# Gas.net
KiCad netlist of a schematic drawn in EAGLE
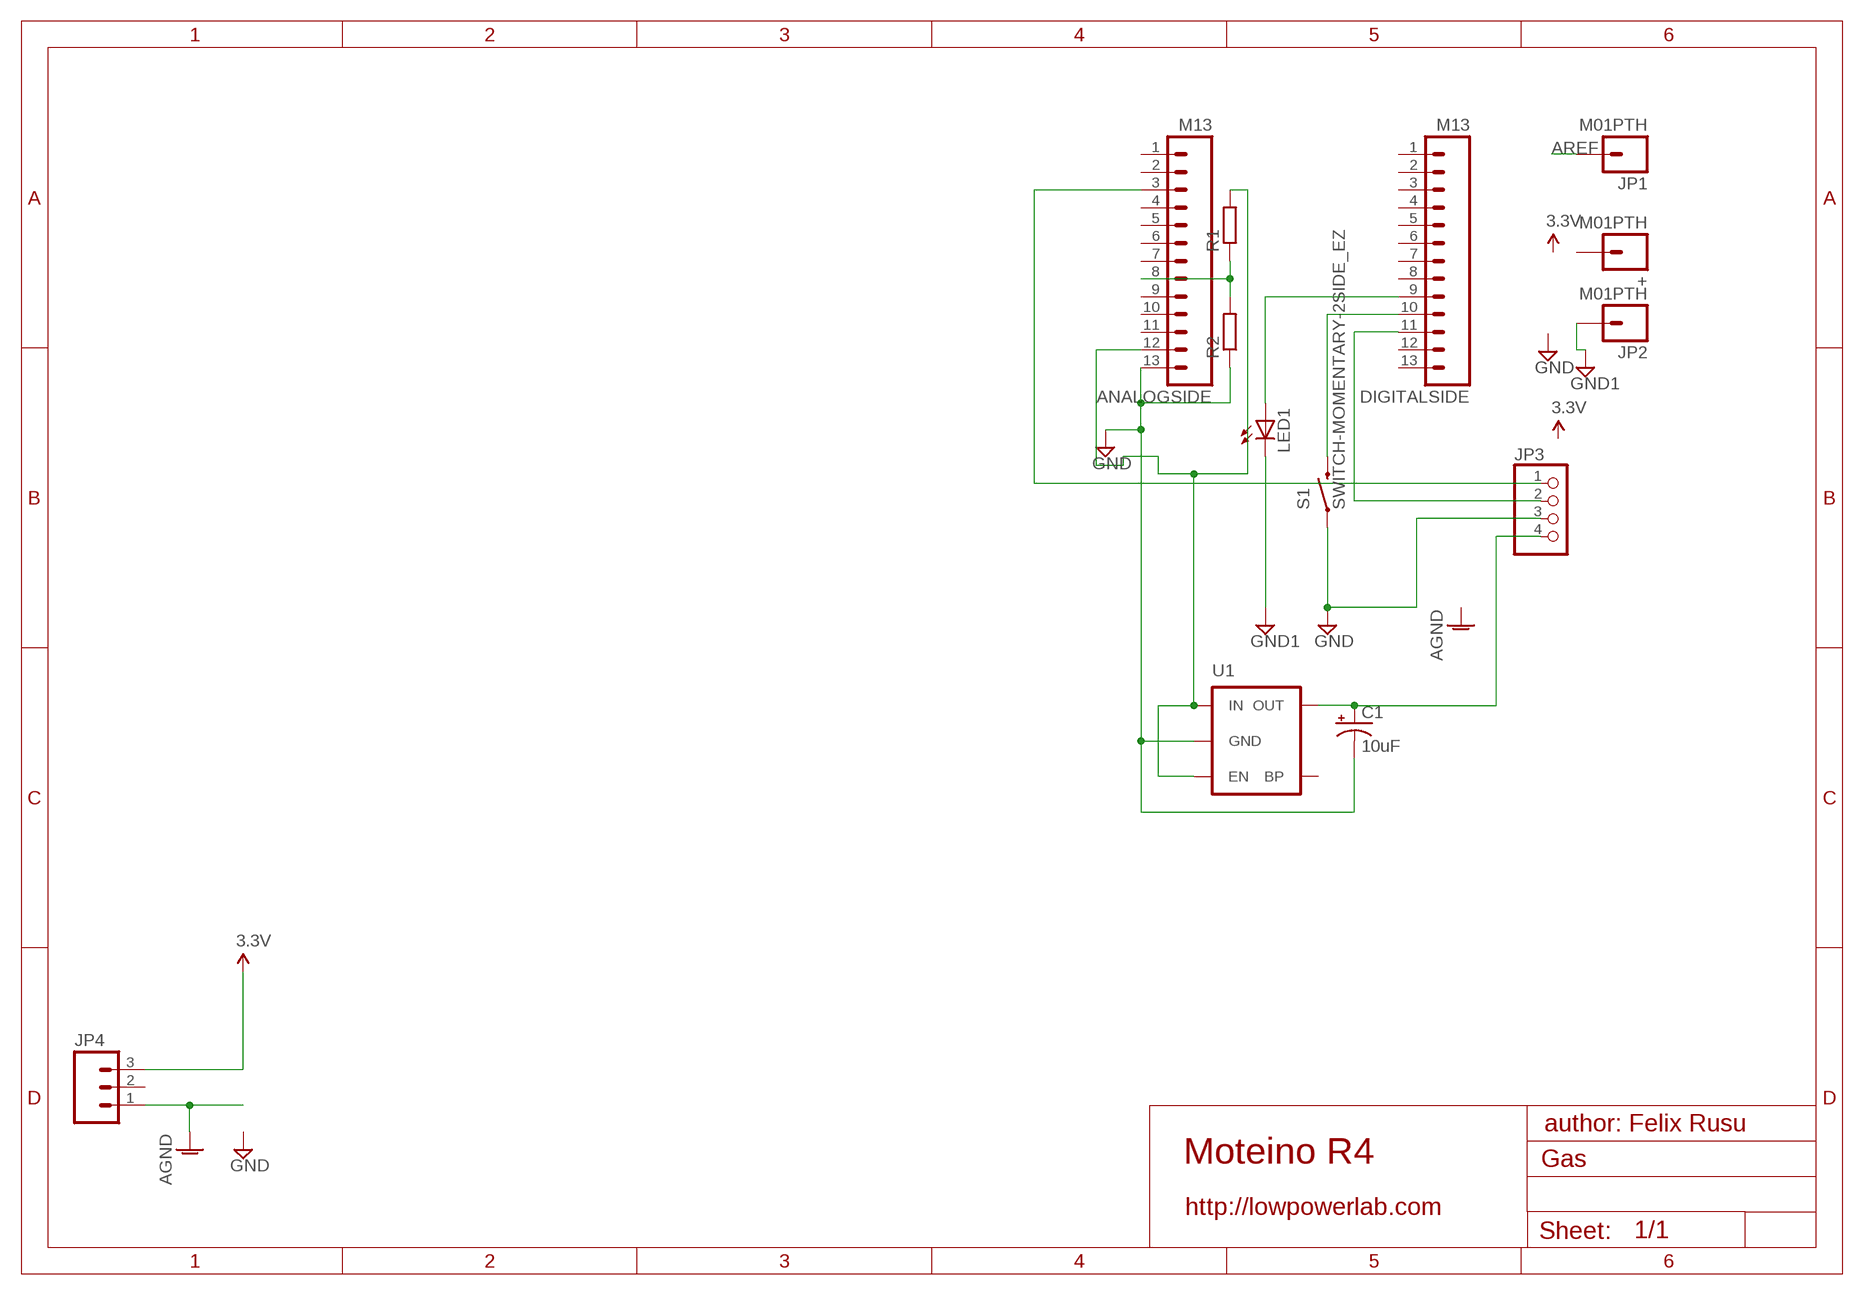
[diagram p0: schematic, sheet 1]

(export (version "E")
  (design (tool "Eeschema 10.0.6"))
  (components
    (comp (ref "+")
      (value "M01PTH")
      (footprint "eagle-import:1X01")
      (libsource (lib "eagle-import") (part "M01PTH"))
    )
    (comp (ref "ANALOGSIDE")
      (value "M13")
      (footprint "eagle-import:1X13")
      (libsource (lib "eagle-import") (part "M13"))
    )
    (comp (ref "C1")
      (value "10uF")
      (footprint "eagle-import:EIA3216")
      (libsource (lib "eagle-import") (part "10UF-16V-10%(TANT)"))
    )
    (comp (ref "DIGITALSIDE")
      (value "M13")
      (footprint "eagle-import:1X13")
      (libsource (lib "eagle-import") (part "M13"))
    )
    (comp (ref "JP1")
      (value "M01PTH")
      (footprint "eagle-import:1X01")
      (libsource (lib "eagle-import") (part "M01PTH"))
    )
    (comp (ref "JP2")
      (value "M01PTH")
      (footprint "eagle-import:1X01")
      (libsource (lib "eagle-import") (part "M01PTH"))
    )
    (comp (ref "JP3")
      (value "PINHD-1X4")
      (footprint "eagle-import:1X04")
      (libsource (lib "eagle-import") (part "PINHD-1X4"))
    )
    (comp (ref "JP4")
      (value "M03PTH")
      (footprint "eagle-import:1X03")
      (libsource (lib "eagle-import") (part "M03PTH"))
    )
    (comp (ref "LED1")
      (value "LED3MM")
      (footprint "eagle-import:LED3MM")
      (libsource (lib "eagle-import") (part "LED3MM"))
    )
    (comp (ref "R1")
      (value "R-EU_0204/7")
      (footprint "eagle-import:0204_7")
      (libsource (lib "eagle-import") (part "R-EU_0204/7"))
    )
    (comp (ref "R2")
      (value "R-EU_0204/7")
      (footprint "eagle-import:0204_7")
      (libsource (lib "eagle-import") (part "R-EU_0204/7"))
    )
    (comp (ref "S1")
      (value "SWITCH-MOMENTARY-2SIDE_EZ")
      (footprint "eagle-import:TACTILE-PTH-SIDEEZ")
      (libsource (lib "eagle-import") (part "SWITCH-MOMENTARY-2SIDE_EZ"))
    )
    (comp (ref "U1")
      (value "MIC52055V")
      (footprint "eagle-import:SOT23-5")
      (libsource (lib "eagle-import") (part "MIC52055V"))
    )
  )
  (nets
    (net (code "1") (name "/AREF") (class "Default")
      (node (ref "JP1") (pin "1") (pinfunction "1_1") (pintype "passive"))
    )
    (net (code "2") (name "3.3V") (class "Default")
      (node (ref "JP4") (pin "3") (pinfunction "3_3") (pintype "passive"))
    )
    (net (code "3") (name "AGND") (class "Default")
      (node (ref "JP4") (pin "1") (pinfunction "1_1") (pintype "passive"))
    )
    (net (code "4") (name "GND") (class "Default")
      (node (ref "ANALOGSIDE") (pin "13") (pinfunction "13_13") (pintype "passive"))
      (node (ref "C1") (pin "C") (pinfunction "-_C") (pintype "passive"))
      (node (ref "JP3") (pin "3") (pinfunction "3_3") (pintype "passive"))
      (node (ref "R2") (pin "1") (pinfunction "1_1") (pintype "passive"))
      (node (ref "S1") (pin "1") (pinfunction "1_1") (pintype "passive"))
      (node (ref "U1") (pin "2") (pinfunction "GND_2") (pintype "input"))
    )
    (net (code "5") (name "GND1") (class "Default")
      (node (ref "JP2") (pin "1") (pinfunction "1_1") (pintype "passive"))
      (node (ref "LED1") (pin "K") (pinfunction "C_K") (pintype "passive"))
    )
    (net (code "6") (name "Net-(ANALOGSIDE-Pad3)") (class "Default")
      (node (ref "ANALOGSIDE") (pin "3") (pinfunction "3_3") (pintype "passive"))
      (node (ref "JP3") (pin "1") (pinfunction "1_1") (pintype "passive"))
    )
    (net (code "7") (name "Net-(ANALOGSIDE-Pad8)") (class "Default")
      (node (ref "ANALOGSIDE") (pin "8") (pinfunction "8_8") (pintype "passive"))
      (node (ref "R1") (pin "1") (pinfunction "1_1") (pintype "passive"))
      (node (ref "R2") (pin "2") (pinfunction "2_2") (pintype "passive"))
    )
    (net (code "8") (name "Net-(C1-+)") (class "Default")
      (node (ref "C1") (pin "A") (pinfunction "+_A") (pintype "passive"))
      (node (ref "JP3") (pin "4") (pinfunction "4_4") (pintype "passive"))
      (node (ref "U1") (pin "5") (pinfunction "OUT_5") (pintype "passive"))
    )
    (net (code "9") (name "Net-(DIGITALSIDE-Pad9)") (class "Default")
      (node (ref "DIGITALSIDE") (pin "9") (pinfunction "9_9") (pintype "passive"))
      (node (ref "LED1") (pin "A") (pinfunction "A_A") (pintype "passive"))
    )
    (net (code "10") (name "Net-(DIGITALSIDE-Pad10)") (class "Default")
      (node (ref "DIGITALSIDE") (pin "10") (pinfunction "10_10") (pintype "passive"))
      (node (ref "S1") (pin "2") (pinfunction "2_2") (pintype "passive"))
    )
    (net (code "11") (name "Net-(DIGITALSIDE-Pad11)") (class "Default")
      (node (ref "DIGITALSIDE") (pin "11") (pinfunction "11_11") (pintype "passive"))
      (node (ref "JP3") (pin "2") (pinfunction "2_2") (pintype "passive"))
    )
    (net (code "12") (name "Net-(U1-EN)") (class "Default")
      (node (ref "ANALOGSIDE") (pin "12") (pinfunction "12_12") (pintype "passive"))
      (node (ref "R1") (pin "2") (pinfunction "2_2") (pintype "passive"))
      (node (ref "U1") (pin "1") (pinfunction "IN_1") (pintype "input"))
      (node (ref "U1") (pin "3") (pinfunction "EN_3") (pintype "input"))
    )
    (net (code "13") (name "unconnected-(+-Pad1)") (class "Default")
      (node (ref "+") (pin "1") (pinfunction "1_1") (pintype "passive"))
    )
    (net (code "14") (name "unconnected-(ANALOGSIDE-Pad1)") (class "Default")
      (node (ref "ANALOGSIDE") (pin "1") (pinfunction "1_1") (pintype "passive"))
    )
    (net (code "15") (name "unconnected-(ANALOGSIDE-Pad2)") (class "Default")
      (node (ref "ANALOGSIDE") (pin "2") (pinfunction "2_2") (pintype "passive"))
    )
    (net (code "16") (name "unconnected-(ANALOGSIDE-Pad4)") (class "Default")
      (node (ref "ANALOGSIDE") (pin "4") (pinfunction "4_4") (pintype "passive"))
    )
    (net (code "17") (name "unconnected-(ANALOGSIDE-Pad5)") (class "Default")
      (node (ref "ANALOGSIDE") (pin "5") (pinfunction "5_5") (pintype "passive"))
    )
    (net (code "18") (name "unconnected-(ANALOGSIDE-Pad6)") (class "Default")
      (node (ref "ANALOGSIDE") (pin "6") (pinfunction "6_6") (pintype "passive"))
    )
    (net (code "19") (name "unconnected-(ANALOGSIDE-Pad7)") (class "Default")
      (node (ref "ANALOGSIDE") (pin "7") (pinfunction "7_7") (pintype "passive"))
    )
    (net (code "20") (name "unconnected-(ANALOGSIDE-Pad9)") (class "Default")
      (node (ref "ANALOGSIDE") (pin "9") (pinfunction "9_9") (pintype "passive"))
    )
    (net (code "21") (name "unconnected-(ANALOGSIDE-Pad10)") (class "Default")
      (node (ref "ANALOGSIDE") (pin "10") (pinfunction "10_10") (pintype "passive"))
    )
    (net (code "22") (name "unconnected-(ANALOGSIDE-Pad11)") (class "Default")
      (node (ref "ANALOGSIDE") (pin "11") (pinfunction "11_11") (pintype "passive"))
    )
    (net (code "23") (name "unconnected-(DIGITALSIDE-Pad1)") (class "Default")
      (node (ref "DIGITALSIDE") (pin "1") (pinfunction "1_1") (pintype "passive"))
    )
    (net (code "24") (name "unconnected-(DIGITALSIDE-Pad2)") (class "Default")
      (node (ref "DIGITALSIDE") (pin "2") (pinfunction "2_2") (pintype "passive"))
    )
    (net (code "25") (name "unconnected-(DIGITALSIDE-Pad3)") (class "Default")
      (node (ref "DIGITALSIDE") (pin "3") (pinfunction "3_3") (pintype "passive"))
    )
    (net (code "26") (name "unconnected-(DIGITALSIDE-Pad4)") (class "Default")
      (node (ref "DIGITALSIDE") (pin "4") (pinfunction "4_4") (pintype "passive"))
    )
    (net (code "27") (name "unconnected-(DIGITALSIDE-Pad5)") (class "Default")
      (node (ref "DIGITALSIDE") (pin "5") (pinfunction "5_5") (pintype "passive"))
    )
    (net (code "28") (name "unconnected-(DIGITALSIDE-Pad6)") (class "Default")
      (node (ref "DIGITALSIDE") (pin "6") (pinfunction "6_6") (pintype "passive"))
    )
    (net (code "29") (name "unconnected-(DIGITALSIDE-Pad7)") (class "Default")
      (node (ref "DIGITALSIDE") (pin "7") (pinfunction "7_7") (pintype "passive"))
    )
    (net (code "30") (name "unconnected-(DIGITALSIDE-Pad8)") (class "Default")
      (node (ref "DIGITALSIDE") (pin "8") (pinfunction "8_8") (pintype "passive"))
    )
    (net (code "31") (name "unconnected-(DIGITALSIDE-Pad12)") (class "Default")
      (node (ref "DIGITALSIDE") (pin "12") (pinfunction "12_12") (pintype "passive"))
    )
    (net (code "32") (name "unconnected-(DIGITALSIDE-Pad13)") (class "Default")
      (node (ref "DIGITALSIDE") (pin "13") (pinfunction "13_13") (pintype "passive"))
    )
    (net (code "33") (name "unconnected-(JP4-Pad2)") (class "Default")
      (node (ref "JP4") (pin "2") (pinfunction "2_2") (pintype "passive"))
    )
    (net (code "34") (name "unconnected-(U1-BP-Pad4)") (class "Default")
      (node (ref "U1") (pin "4") (pinfunction "BP_4") (pintype "input"))
    )
  )
)
